# uC_power.net
KiCad netlist of a schematic drawn in EAGLE
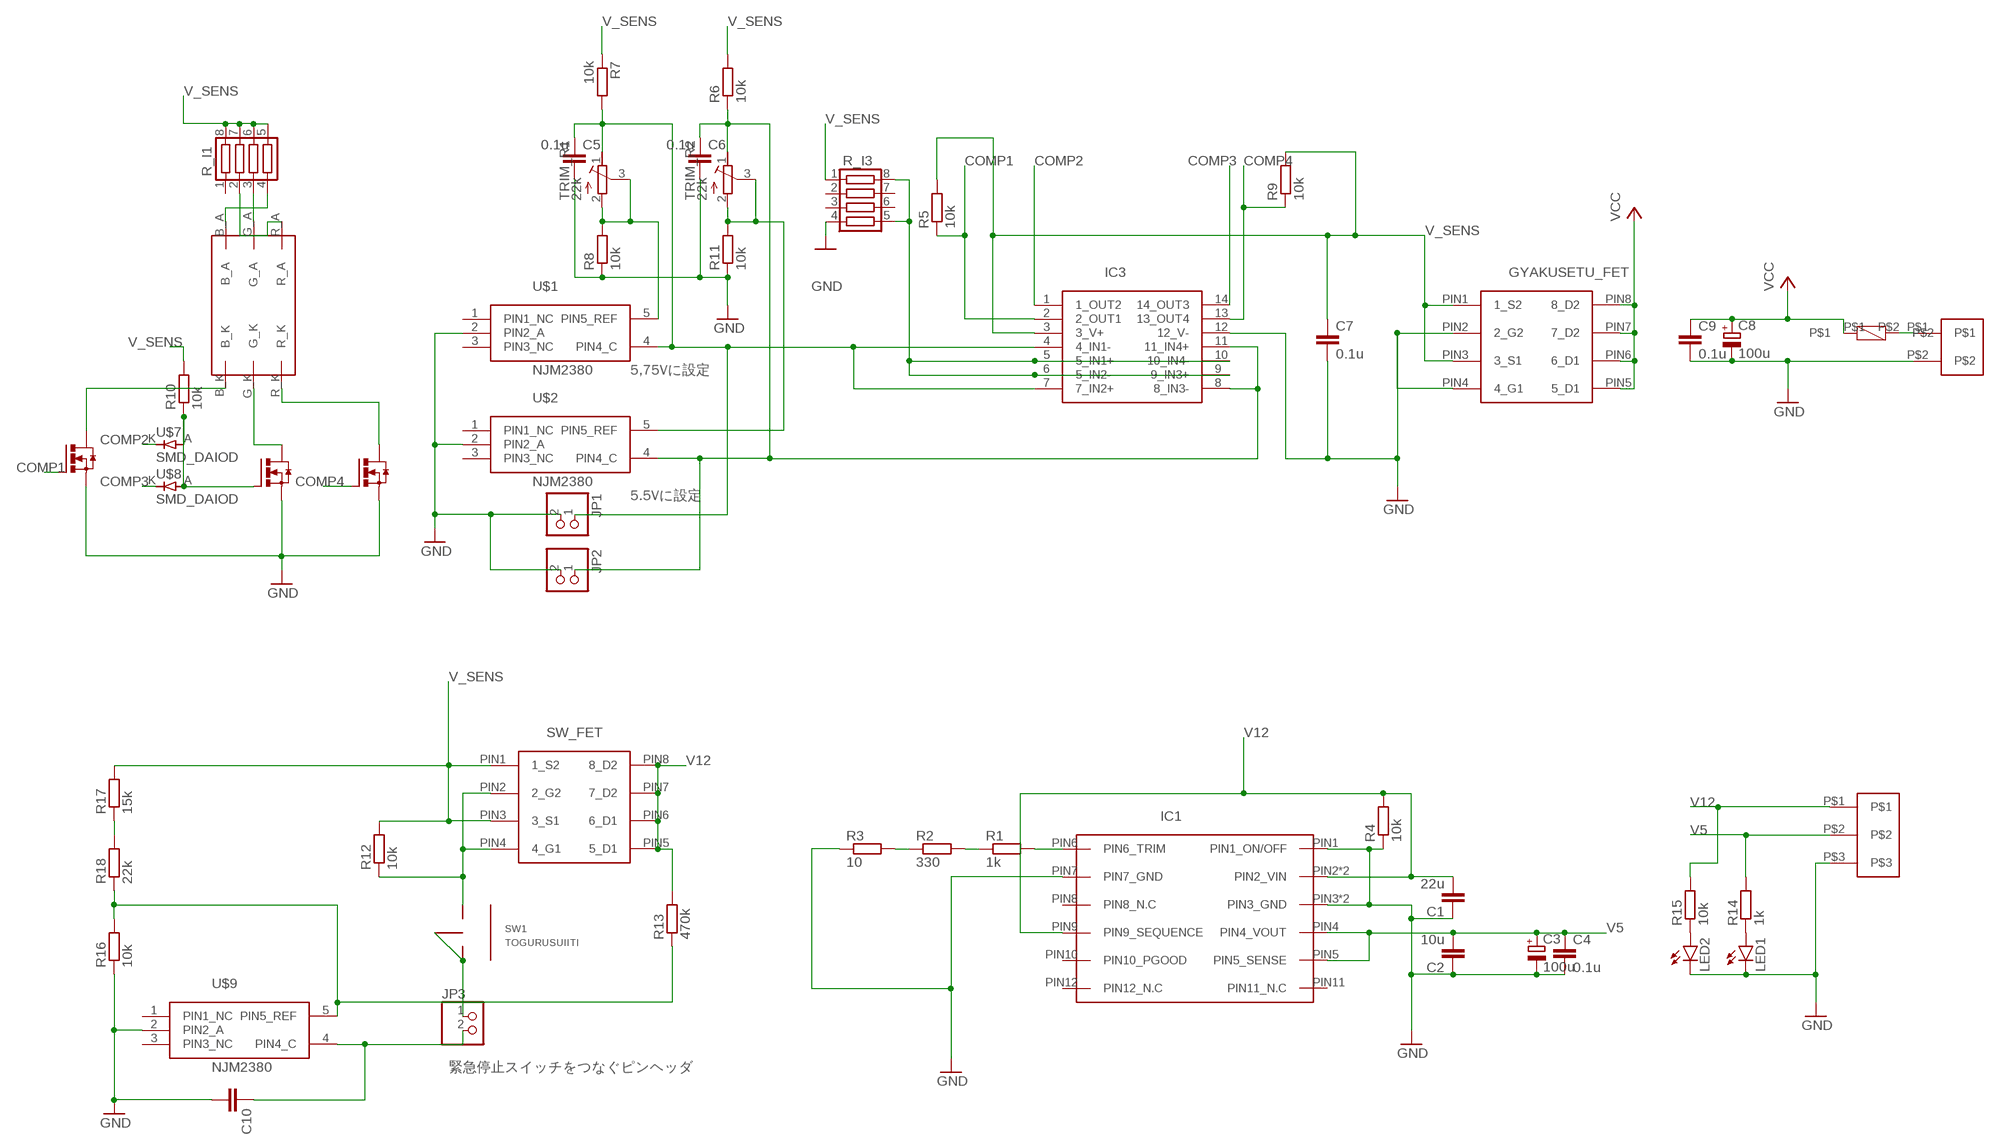
[diagram p0: schematic, sheet 1]

(export (version "E")
  (design (tool "Eeschema 10.0.6"))
  (components
    (comp (ref "C1")
      (value "22u")
      (footprint "eagle-import:C1608")
      (libsource (lib "eagle-import") (part "C-EUC1608"))
    )
    (comp (ref "C2")
      (value "10u")
      (footprint "eagle-import:C1608")
      (libsource (lib "eagle-import") (part "C-EUC1608"))
    )
    (comp (ref "C3")
      (value "100u")
      (footprint "eagle-import:153CLV-0605")
      (libsource (lib "eagle-import") (part "CPOL-EU153CLV-0605"))
    )
    (comp (ref "C4")
      (value "0.1u")
      (footprint "eagle-import:C1608")
      (libsource (lib "eagle-import") (part "C-EUC1608"))
    )
    (comp (ref "C5")
      (value "0.1u")
      (footprint "eagle-import:C1608")
      (libsource (lib "eagle-import") (part "C-EUC1608"))
    )
    (comp (ref "C6")
      (value "0.1u")
      (footprint "eagle-import:C1608")
      (libsource (lib "eagle-import") (part "C-EUC1608"))
    )
    (comp (ref "C7")
      (value "0.1u")
      (footprint "eagle-import:C1608")
      (libsource (lib "eagle-import") (part "C-EUC1608"))
    )
    (comp (ref "C8")
      (value "100u")
      (footprint "eagle-import:153CLV-0605")
      (libsource (lib "eagle-import") (part "CPOL-EU153CLV-0605"))
    )
    (comp (ref "C9")
      (value "0.1u")
      (footprint "eagle-import:C1608")
      (libsource (lib "eagle-import") (part "C-EUC1608"))
    )
    (comp (ref "C10")
      (value "C-EUC1608")
      (footprint "eagle-import:C1608")
      (libsource (lib "eagle-import") (part "C-EUC1608"))
    )
    (comp (ref "F1")
      (value "RGEF300")
      (footprint "eagle-import:RGEF300")
      (libsource (lib "eagle-import") (part "RGEF300"))
    )
    (comp (ref "GYAKUSETU_FET")
      (value "FDS4935A")
      (footprint "eagle-import:SOP8")
      (libsource (lib "eagle-import") (part "FDS4935A"))
    )
    (comp (ref "IC1")
      (value "MURATA_OKL-T/6-W12N-C")
      (footprint "eagle-import:OKL-T_6-W12N-C")
      (libsource (lib "eagle-import") (part "MURATA_OKL-T/6-W12N-C"))
    )
    (comp (ref "IC3")
      (value "UPC339GR")
      (footprint "eagle-import:TSSOP14")
      (libsource (lib "eagle-import") (part "UPC339GR"))
    )
    (comp (ref "JP1")
      (value "PINHD-1X2")
      (footprint "eagle-import:1X02")
      (libsource (lib "eagle-import") (part "PINHD-1X2"))
    )
    (comp (ref "JP2")
      (value "PINHD-1X2")
      (footprint "eagle-import:1X02")
      (libsource (lib "eagle-import") (part "PINHD-1X2"))
    )
    (comp (ref "JP3")
      (value "PINHD-1X2")
      (footprint "eagle-import:1X02")
      (libsource (lib "eagle-import") (part "PINHD-1X2"))
    )
    (comp (ref "LED1")
      (value "1608LED")
      (footprint "eagle-import:1608")
      (libsource (lib "eagle-import") (part "1608LED"))
    )
    (comp (ref "LED2")
      (value "1608LED")
      (footprint "eagle-import:1608")
      (libsource (lib "eagle-import") (part "1608LED"))
    )
    (comp (ref "R1")
      (value "1k")
      (footprint "eagle-import:1608")
      (libsource (lib "eagle-import") (part "R_REG"))
    )
    (comp (ref "R2")
      (value "330")
      (footprint "eagle-import:1608")
      (libsource (lib "eagle-import") (part "R_REG"))
    )
    (comp (ref "R3")
      (value "10")
      (footprint "eagle-import:1608")
      (libsource (lib "eagle-import") (part "R_REG"))
    )
    (comp (ref "R4")
      (value "10k")
      (footprint "eagle-import:1608")
      (libsource (lib "eagle-import") (part "R_REG"))
    )
    (comp (ref "R5")
      (value "10k")
      (footprint "eagle-import:1608")
      (libsource (lib "eagle-import") (part "R_REG"))
    )
    (comp (ref "R6")
      (value "10k")
      (footprint "eagle-import:1608")
      (libsource (lib "eagle-import") (part "R_REG"))
    )
    (comp (ref "R7")
      (value "10k")
      (footprint "eagle-import:1608")
      (libsource (lib "eagle-import") (part "R_REG"))
    )
    (comp (ref "R8")
      (value "10k")
      (footprint "eagle-import:1608")
      (libsource (lib "eagle-import") (part "R_REG"))
    )
    (comp (ref "R9")
      (value "10k")
      (footprint "eagle-import:1608")
      (libsource (lib "eagle-import") (part "R_REG"))
    )
    (comp (ref "R10")
      (value "10k")
      (footprint "eagle-import:1608")
      (libsource (lib "eagle-import") (part "R_REG"))
    )
    (comp (ref "R11")
      (value "10k")
      (footprint "eagle-import:1608")
      (libsource (lib "eagle-import") (part "R_REG"))
    )
    (comp (ref "R12")
      (value "10k")
      (footprint "eagle-import:1608")
      (libsource (lib "eagle-import") (part "R_REG"))
    )
    (comp (ref "R13")
      (value "470k")
      (footprint "eagle-import:1608")
      (libsource (lib "eagle-import") (part "R_REG"))
    )
    (comp (ref "R14")
      (value "1k")
      (footprint "eagle-import:1608")
      (libsource (lib "eagle-import") (part "R_REG"))
    )
    (comp (ref "R15")
      (value "10k")
      (footprint "eagle-import:1608")
      (libsource (lib "eagle-import") (part "R_REG"))
    )
    (comp (ref "R16")
      (value "10k")
      (footprint "eagle-import:1608")
      (libsource (lib "eagle-import") (part "R_REG"))
    )
    (comp (ref "R17")
      (value "15k")
      (footprint "eagle-import:1608")
      (libsource (lib "eagle-import") (part "R_REG"))
    )
    (comp (ref "R18")
      (value "22k")
      (footprint "eagle-import:1608")
      (libsource (lib "eagle-import") (part "R_REG"))
    )
    (comp (ref "R_I1")
      (value "R_SHUGOU2")
      (footprint "eagle-import:1005X4RESISTOR")
      (libsource (lib "eagle-import") (part "R_SHUGOU2"))
    )
    (comp (ref "R_I3")
      (value "R_SHUGOU2")
      (footprint "eagle-import:1005X4RESISTOR")
      (libsource (lib "eagle-import") (part "R_SHUGOU2"))
    )
    (comp (ref "SW1")
      (value "TOGURUSUIITI")
      (footprint "eagle-import:TOGURUSUIITI")
      (libsource (lib "eagle-import") (part "TOGURUSUIITI"))
    )
    (comp (ref "SW_FET")
      (value "FDS4935A")
      (footprint "eagle-import:SOP8")
      (libsource (lib "eagle-import") (part "FDS4935A"))
    )
    (comp (ref "TRIM_R1")
      (value "22k")
      (footprint "eagle-import:PV23A")
      (libsource (lib "eagle-import") (part "R_TRIM2"))
    )
    (comp (ref "TRIM_R2")
      (value "22k")
      (footprint "eagle-import:PV23A")
      (libsource (lib "eagle-import") (part "R_TRIM2"))
    )
    (comp (ref "U$1")
      (value "NJM2380")
      (footprint "eagle-import:SOT23-5")
      (libsource (lib "eagle-import") (part "NJM2380"))
    )
    (comp (ref "U$2")
      (value "NJM2380")
      (footprint "eagle-import:SOT23-5")
      (libsource (lib "eagle-import") (part "NJM2380"))
    )
    (comp (ref "U$3")
      (value "SOT23_NFET")
      (footprint "eagle-import:SOT23")
      (libsource (lib "eagle-import") (part "SOT23_NFET"))
    )
    (comp (ref "U$4")
      (value "SOT23_NFET")
      (footprint "eagle-import:SOT23")
      (libsource (lib "eagle-import") (part "SOT23_NFET"))
    )
    (comp (ref "U$5")
      (value "SOT23_NFET")
      (footprint "eagle-import:SOT23")
      (libsource (lib "eagle-import") (part "SOT23_NFET"))
    )
    (comp (ref "U$6")
      (value "RGB_LED")
      (footprint "eagle-import:RGB_LED")
      (libsource (lib "eagle-import") (part "RGB_LED"))
    )
    (comp (ref "U$7")
      (value "SMD_DAIOD")
      (footprint "eagle-import:SOD_123")
      (libsource (lib "eagle-import") (part "SMD_DAIOD"))
    )
    (comp (ref "U$8")
      (value "SMD_DAIOD")
      (footprint "eagle-import:SOD_123")
      (libsource (lib "eagle-import") (part "SMD_DAIOD"))
    )
    (comp (ref "U$9")
      (value "NJM2380")
      (footprint "eagle-import:SOT23-5")
      (libsource (lib "eagle-import") (part "NJM2380"))
    )
    (comp (ref "U$10")
      (value "YUROBLOCK3")
      (footprint "eagle-import:YUROBLOCK3")
      (libsource (lib "eagle-import") (part "YUROBLOCK3"))
    )
    (comp (ref "U$11")
      (value "YUROBLOCK2")
      (footprint "eagle-import:YUROBLOCK2")
      (libsource (lib "eagle-import") (part "YUROBLOCK2"))
    )
  )
  (nets
    (net (code "1") (name "/COMP1") (class "Default")
      (node (ref "IC3") (pin "2") (pinfunction "2_OUT1_2") (pintype "bidirectional"))
      (node (ref "R5") (pin "1") (pinfunction "1_1") (pintype "passive"))
      (node (ref "U$5") (pin "PIN1") (pinfunction "PIN1_G_PIN1") (pintype "passive"))
    )
    (net (code "2") (name "/COMP2") (class "Default")
      (node (ref "IC3") (pin "1") (pinfunction "1_OUT2_1") (pintype "bidirectional"))
      (node (ref "U$7") (pin "K") (pinfunction "C_K") (pintype "passive"))
    )
    (net (code "3") (name "/COMP3") (class "Default")
      (node (ref "IC3") (pin "14") (pinfunction "14_OUT3_14") (pintype "bidirectional"))
      (node (ref "U$8") (pin "K") (pinfunction "C_K") (pintype "passive"))
    )
    (net (code "4") (name "/COMP4") (class "Default")
      (node (ref "IC3") (pin "13") (pinfunction "13_OUT4_13") (pintype "bidirectional"))
      (node (ref "R9") (pin "1") (pinfunction "1_1") (pintype "passive"))
      (node (ref "U$3") (pin "PIN1") (pinfunction "PIN1_G_PIN1") (pintype "passive"))
    )
    (net (code "5") (name "/V5") (class "Default")
      (node (ref "C2") (pin "2") (pinfunction "2_2") (pintype "passive"))
      (node (ref "C3") (pin "+") (pinfunction "+_+") (pintype "passive"))
      (node (ref "C4") (pin "1") (pinfunction "1_1") (pintype "passive"))
      (node (ref "IC1") (pin "PIN4") (pinfunction "PIN4_VOUT_PIN4") (pintype "bidirectional"))
      (node (ref "IC1") (pin "PIN5") (pinfunction "PIN5_SENSE_PIN5") (pintype "bidirectional"))
      (node (ref "R14") (pin "2") (pinfunction "2_2") (pintype "passive"))
      (node (ref "U$10") (pin "P$2") (pinfunction "P$2_P$2") (pintype "bidirectional"))
    )
    (net (code "6") (name "/V12") (class "Default")
      (node (ref "C1") (pin "2") (pinfunction "2_2") (pintype "passive"))
      (node (ref "IC1") (pin "PIN2") (pinfunction "PIN2_VIN_PIN2") (pintype "bidirectional"))
      (node (ref "IC1") (pin "PIN2@2") (pinfunction "PIN2_VIN_PIN2@2") (pintype "bidirectional"))
      (node (ref "IC1") (pin "PIN9") (pinfunction "PIN9_SEQUENCE_PIN9") (pintype "bidirectional"))
      (node (ref "R13") (pin "2") (pinfunction "2_2") (pintype "passive"))
      (node (ref "R15") (pin "2") (pinfunction "2_2") (pintype "passive"))
      (node (ref "R4") (pin "2") (pinfunction "2_2") (pintype "passive"))
      (node (ref "SW_FET") (pin "PIN5") (pinfunction "5_D1_PIN5") (pintype "bidirectional"))
      (node (ref "SW_FET") (pin "PIN6") (pinfunction "6_D1_PIN6") (pintype "bidirectional"))
      (node (ref "SW_FET") (pin "PIN7") (pinfunction "7_D2_PIN7") (pintype "bidirectional"))
      (node (ref "SW_FET") (pin "PIN8") (pinfunction "8_D2_PIN8") (pintype "bidirectional"))
      (node (ref "U$10") (pin "P$1") (pinfunction "P$1_P$1") (pintype "bidirectional"))
    )
    (net (code "7") (name "/V_SENS") (class "Default")
      (node (ref "C7") (pin "1") (pinfunction "1_1") (pintype "passive"))
      (node (ref "GYAKUSETU_FET") (pin "PIN1") (pinfunction "1_S2_PIN1") (pintype "bidirectional"))
      (node (ref "GYAKUSETU_FET") (pin "PIN3") (pinfunction "3_S1_PIN3") (pintype "bidirectional"))
      (node (ref "IC3") (pin "3") (pinfunction "3_V+_3") (pintype "bidirectional"))
      (node (ref "R10") (pin "2") (pinfunction "2_2") (pintype "passive"))
      (node (ref "R12") (pin "2") (pinfunction "2_2") (pintype "passive"))
      (node (ref "R17") (pin "2") (pinfunction "2_2") (pintype "passive"))
      (node (ref "R5") (pin "2") (pinfunction "2_2") (pintype "passive"))
      (node (ref "R6") (pin "2") (pinfunction "2_2") (pintype "passive"))
      (node (ref "R7") (pin "1") (pinfunction "1_1") (pintype "passive"))
      (node (ref "R9") (pin "2") (pinfunction "2_2") (pintype "passive"))
      (node (ref "R_I1") (pin "5") (pinfunction "5_5") (pintype "passive"))
      (node (ref "R_I1") (pin "6") (pinfunction "6_6") (pintype "passive"))
      (node (ref "R_I1") (pin "7") (pinfunction "7_7") (pintype "passive"))
      (node (ref "R_I1") (pin "8") (pinfunction "8_8") (pintype "passive"))
      (node (ref "R_I3") (pin "1") (pinfunction "1_1") (pintype "passive"))
      (node (ref "SW_FET") (pin "PIN1") (pinfunction "1_S2_PIN1") (pintype "bidirectional"))
      (node (ref "SW_FET") (pin "PIN3") (pinfunction "3_S1_PIN3") (pintype "bidirectional"))
    )
    (net (code "8") (name "GND") (class "Default")
      (node (ref "C1") (pin "1") (pinfunction "1_1") (pintype "passive"))
      (node (ref "C10") (pin "2") (pinfunction "2_2") (pintype "passive"))
      (node (ref "C2") (pin "1") (pinfunction "1_1") (pintype "passive"))
      (node (ref "C3") (pin "-") (pinfunction "-_-") (pintype "passive"))
      (node (ref "C4") (pin "2") (pinfunction "2_2") (pintype "passive"))
      (node (ref "C5") (pin "2") (pinfunction "2_2") (pintype "passive"))
      (node (ref "C6") (pin "2") (pinfunction "2_2") (pintype "passive"))
      (node (ref "C7") (pin "2") (pinfunction "2_2") (pintype "passive"))
      (node (ref "C8") (pin "-") (pinfunction "-_-") (pintype "passive"))
      (node (ref "C9") (pin "2") (pinfunction "2_2") (pintype "passive"))
      (node (ref "GYAKUSETU_FET") (pin "PIN2") (pinfunction "2_G2_PIN2") (pintype "bidirectional"))
      (node (ref "GYAKUSETU_FET") (pin "PIN4") (pinfunction "4_G1_PIN4") (pintype "bidirectional"))
      (node (ref "IC1") (pin "PIN1") (pinfunction "PIN1_ON/OFF_PIN1") (pintype "bidirectional"))
      (node (ref "IC1") (pin "PIN3") (pinfunction "PIN3_GND_PIN3") (pintype "bidirectional"))
      (node (ref "IC1") (pin "PIN3@2") (pinfunction "PIN3_GND_PIN3@2") (pintype "bidirectional"))
      (node (ref "IC1") (pin "PIN7") (pinfunction "PIN7_GND_PIN7") (pintype "bidirectional"))
      (node (ref "IC3") (pin "12") (pinfunction "12_V-_12") (pintype "bidirectional"))
      (node (ref "JP1") (pin "2") (pinfunction "2_2") (pintype "passive"))
      (node (ref "JP2") (pin "2") (pinfunction "2_2") (pintype "passive"))
      (node (ref "LED1") (pin "K") (pinfunction "K_K") (pintype "passive"))
      (node (ref "LED2") (pin "K") (pinfunction "K_K") (pintype "passive"))
      (node (ref "R11") (pin "1") (pinfunction "1_1") (pintype "passive"))
      (node (ref "R16") (pin "1") (pinfunction "1_1") (pintype "passive"))
      (node (ref "R3") (pin "1") (pinfunction "1_1") (pintype "passive"))
      (node (ref "R4") (pin "1") (pinfunction "1_1") (pintype "passive"))
      (node (ref "R8") (pin "1") (pinfunction "1_1") (pintype "passive"))
      (node (ref "R_I3") (pin "4") (pinfunction "4_4") (pintype "passive"))
      (node (ref "U$1") (pin "2") (pinfunction "PIN2_A_2") (pintype "bidirectional"))
      (node (ref "U$10") (pin "P$3") (pinfunction "P$3_P$3") (pintype "bidirectional"))
      (node (ref "U$11") (pin "P$2") (pinfunction "P$2_P$2") (pintype "bidirectional"))
      (node (ref "U$2") (pin "2") (pinfunction "PIN2_A_2") (pintype "bidirectional"))
      (node (ref "U$3") (pin "PIN2") (pinfunction "PIN3_S_PIN2") (pintype "passive"))
      (node (ref "U$4") (pin "PIN2") (pinfunction "PIN3_S_PIN2") (pintype "passive"))
      (node (ref "U$5") (pin "PIN2") (pinfunction "PIN3_S_PIN2") (pintype "passive"))
      (node (ref "U$9") (pin "2") (pinfunction "PIN2_A_2") (pintype "bidirectional"))
    )
    (net (code "9") (name "Net-(F1-PadP$2)") (class "Default")
      (node (ref "F1") (pin "P$2") (pinfunction "P$2_P$2") (pintype "bidirectional"))
      (node (ref "U$11") (pin "P$1") (pinfunction "P$1_P$1") (pintype "bidirectional"))
    )
    (net (code "10") (name "Net-(IC1-PIN6_TRIM)") (class "Default")
      (node (ref "IC1") (pin "PIN6") (pinfunction "PIN6_TRIM_PIN6") (pintype "bidirectional"))
      (node (ref "R1") (pin "2") (pinfunction "2_2") (pintype "passive"))
    )
    (net (code "11") (name "Net-(IC3-4_IN1-)") (class "Default")
      (node (ref "C5") (pin "1") (pinfunction "1_1") (pintype "passive"))
      (node (ref "IC3") (pin "4") (pinfunction "4_IN1-_4") (pintype "bidirectional"))
      (node (ref "IC3") (pin "7") (pinfunction "7_IN2+_7") (pintype "bidirectional"))
      (node (ref "JP1") (pin "1") (pinfunction "1_1") (pintype "passive"))
      (node (ref "R7") (pin "2") (pinfunction "2_2") (pintype "passive"))
      (node (ref "TRIM_R1") (pin "1") (pinfunction "E_1") (pintype "passive"))
      (node (ref "U$1") (pin "4") (pinfunction "PIN4_C_4") (pintype "bidirectional"))
    )
    (net (code "12") (name "Net-(IC3-10_IN4-)") (class "Default")
      (node (ref "IC3") (pin "10") (pinfunction "10_IN4-_10") (pintype "bidirectional"))
      (node (ref "IC3") (pin "5") (pinfunction "5_IN1+_5") (pintype "bidirectional"))
      (node (ref "IC3") (pin "6") (pinfunction "5_IN2-_6") (pintype "bidirectional"))
      (node (ref "IC3") (pin "9") (pinfunction "9_IN3+_9") (pintype "bidirectional"))
      (node (ref "R_I3") (pin "5") (pinfunction "5_5") (pintype "passive"))
      (node (ref "R_I3") (pin "8") (pinfunction "8_8") (pintype "passive"))
    )
    (net (code "13") (name "Net-(IC3-11_IN4+)") (class "Default")
      (node (ref "C6") (pin "1") (pinfunction "1_1") (pintype "passive"))
      (node (ref "IC3") (pin "11") (pinfunction "11_IN4+_11") (pintype "bidirectional"))
      (node (ref "IC3") (pin "8") (pinfunction "8_IN3-_8") (pintype "bidirectional"))
      (node (ref "JP2") (pin "1") (pinfunction "1_1") (pintype "passive"))
      (node (ref "R6") (pin "1") (pinfunction "1_1") (pintype "passive"))
      (node (ref "TRIM_R2") (pin "1") (pinfunction "E_1") (pintype "passive"))
      (node (ref "U$2") (pin "4") (pinfunction "PIN4_C_4") (pintype "bidirectional"))
    )
    (net (code "14") (name "Net-(JP3-Pad1)") (class "Default")
      (node (ref "JP3") (pin "1") (pinfunction "1_1") (pintype "passive"))
      (node (ref "SW1") (pin "2") (pinfunction "2_2") (pintype "bidirectional"))
      (node (ref "SW1") (pin "C") (pinfunction "C_C") (pintype "bidirectional"))
    )
    (net (code "15") (name "Net-(LED1-PadA)") (class "Default")
      (node (ref "LED1") (pin "A") (pinfunction "A_A") (pintype "passive"))
      (node (ref "R14") (pin "1") (pinfunction "1_1") (pintype "passive"))
    )
    (net (code "16") (name "Net-(LED2-PadA)") (class "Default")
      (node (ref "LED2") (pin "A") (pinfunction "A_A") (pintype "passive"))
      (node (ref "R15") (pin "1") (pinfunction "1_1") (pintype "passive"))
    )
    (net (code "17") (name "Net-(R1-Pad1)") (class "Default")
      (node (ref "R1") (pin "1") (pinfunction "1_1") (pintype "passive"))
      (node (ref "R2") (pin "2") (pinfunction "2_2") (pintype "passive"))
    )
    (net (code "18") (name "Net-(R2-Pad1)") (class "Default")
      (node (ref "R2") (pin "1") (pinfunction "1_1") (pintype "passive"))
      (node (ref "R3") (pin "2") (pinfunction "2_2") (pintype "passive"))
    )
    (net (code "19") (name "Net-(R17-Pad1)") (class "Default")
      (node (ref "R17") (pin "1") (pinfunction "1_1") (pintype "passive"))
      (node (ref "R18") (pin "2") (pinfunction "2_2") (pintype "passive"))
    )
    (net (code "20") (name "Net-(R_I1-Pad2)") (class "Default")
      (node (ref "R_I1") (pin "2") (pinfunction "2_2") (pintype "passive"))
      (node (ref "U$6") (pin "R_A") (pinfunction "R_A_R_A") (pintype "bidirectional"))
    )
    (net (code "21") (name "Net-(R_I1-Pad3)") (class "Default")
      (node (ref "R_I1") (pin "3") (pinfunction "3_3") (pintype "passive"))
      (node (ref "U$6") (pin "G_A") (pinfunction "G_A_G_A") (pintype "bidirectional"))
    )
    (net (code "22") (name "Net-(R_I1-Pad4)") (class "Default")
      (node (ref "R_I1") (pin "4") (pinfunction "4_4") (pintype "passive"))
      (node (ref "U$6") (pin "B_A") (pinfunction "B_A_B_A") (pintype "bidirectional"))
    )
    (net (code "23") (name "Net-(SW_FET-2_G2)") (class "Default")
      (node (ref "R12") (pin "1") (pinfunction "1_1") (pintype "passive"))
      (node (ref "SW1") (pin "1") (pinfunction "1_1") (pintype "bidirectional"))
      (node (ref "SW_FET") (pin "PIN2") (pinfunction "2_G2_PIN2") (pintype "bidirectional"))
      (node (ref "SW_FET") (pin "PIN4") (pinfunction "4_G1_PIN4") (pintype "bidirectional"))
    )
    (net (code "24") (name "Net-(TRIM_R1-A)") (class "Default")
      (node (ref "R8") (pin "2") (pinfunction "2_2") (pintype "passive"))
      (node (ref "TRIM_R1") (pin "2") (pinfunction "A_2") (pintype "passive"))
      (node (ref "TRIM_R1") (pin "3") (pinfunction "S_3") (pintype "passive"))
      (node (ref "U$1") (pin "5") (pinfunction "PIN5_REF_5") (pintype "bidirectional"))
    )
    (net (code "25") (name "Net-(TRIM_R2-A)") (class "Default")
      (node (ref "R11") (pin "2") (pinfunction "2_2") (pintype "passive"))
      (node (ref "TRIM_R2") (pin "2") (pinfunction "A_2") (pintype "passive"))
      (node (ref "TRIM_R2") (pin "3") (pinfunction "S_3") (pintype "passive"))
      (node (ref "U$2") (pin "5") (pinfunction "PIN5_REF_5") (pintype "bidirectional"))
    )
    (net (code "26") (name "Net-(U$3-PIN2_D)") (class "Default")
      (node (ref "U$3") (pin "PIN3") (pinfunction "PIN2_D_PIN3") (pintype "passive"))
      (node (ref "U$6") (pin "R_K") (pinfunction "R_K_R_K") (pintype "bidirectional"))
    )
    (net (code "27") (name "Net-(U$4-PIN1_G)") (class "Default")
      (node (ref "R10") (pin "1") (pinfunction "1_1") (pintype "passive"))
      (node (ref "U$4") (pin "PIN1") (pinfunction "PIN1_G_PIN1") (pintype "passive"))
      (node (ref "U$7") (pin "A") (pinfunction "A_A") (pintype "passive"))
      (node (ref "U$8") (pin "A") (pinfunction "A_A") (pintype "passive"))
    )
    (net (code "28") (name "Net-(U$4-PIN2_D)") (class "Default")
      (node (ref "U$4") (pin "PIN3") (pinfunction "PIN2_D_PIN3") (pintype "passive"))
      (node (ref "U$6") (pin "G_K") (pinfunction "G_K_G_K") (pintype "bidirectional"))
    )
    (net (code "29") (name "Net-(U$5-PIN2_D)") (class "Default")
      (node (ref "U$5") (pin "PIN3") (pinfunction "PIN2_D_PIN3") (pintype "passive"))
      (node (ref "U$6") (pin "B_K") (pinfunction "B_K_B_K") (pintype "bidirectional"))
    )
    (net (code "30") (name "Net-(U$9-PIN4_C)") (class "Default")
      (node (ref "C10") (pin "1") (pinfunction "1_1") (pintype "passive"))
      (node (ref "JP3") (pin "2") (pinfunction "2_2") (pintype "passive"))
      (node (ref "U$9") (pin "4") (pinfunction "PIN4_C_4") (pintype "bidirectional"))
    )
    (net (code "31") (name "Net-(U$9-PIN5_REF)") (class "Default")
      (node (ref "R13") (pin "1") (pinfunction "1_1") (pintype "passive"))
      (node (ref "R16") (pin "2") (pinfunction "2_2") (pintype "passive"))
      (node (ref "R18") (pin "1") (pinfunction "1_1") (pintype "passive"))
      (node (ref "U$9") (pin "5") (pinfunction "PIN5_REF_5") (pintype "bidirectional"))
    )
    (net (code "32") (name "VCC") (class "Default")
      (node (ref "C8") (pin "+") (pinfunction "+_+") (pintype "passive"))
      (node (ref "C9") (pin "1") (pinfunction "1_1") (pintype "passive"))
      (node (ref "F1") (pin "P$1") (pinfunction "P$1_P$1") (pintype "bidirectional"))
      (node (ref "GYAKUSETU_FET") (pin "PIN5") (pinfunction "5_D1_PIN5") (pintype "bidirectional"))
      (node (ref "GYAKUSETU_FET") (pin "PIN6") (pinfunction "6_D1_PIN6") (pintype "bidirectional"))
      (node (ref "GYAKUSETU_FET") (pin "PIN7") (pinfunction "7_D2_PIN7") (pintype "bidirectional"))
      (node (ref "GYAKUSETU_FET") (pin "PIN8") (pinfunction "8_D2_PIN8") (pintype "bidirectional"))
    )
    (net (code "33") (name "unconnected-(IC1-PIN8_N.C-PadPIN8)") (class "Default")
      (node (ref "IC1") (pin "PIN8") (pinfunction "PIN8_N.C_PIN8") (pintype "bidirectional"))
    )
    (net (code "34") (name "unconnected-(IC1-PIN10_PGOOD-PadPIN10)") (class "Default")
      (node (ref "IC1") (pin "PIN10") (pinfunction "PIN10_PGOOD_PIN10") (pintype "bidirectional"))
    )
    (net (code "35") (name "unconnected-(IC1-PIN11_N.C-PadPIN11)") (class "Default")
      (node (ref "IC1") (pin "PIN11") (pinfunction "PIN11_N.C_PIN11") (pintype "bidirectional"))
    )
    (net (code "36") (name "unconnected-(IC1-PIN12_N.C-PadPIN12)") (class "Default")
      (node (ref "IC1") (pin "PIN12") (pinfunction "PIN12_N.C_PIN12") (pintype "bidirectional"))
    )
    (net (code "37") (name "unconnected-(R_I1-Pad1)") (class "Default")
      (node (ref "R_I1") (pin "1") (pinfunction "1_1") (pintype "passive"))
    )
    (net (code "38") (name "unconnected-(R_I3-Pad2)") (class "Default")
      (node (ref "R_I3") (pin "2") (pinfunction "2_2") (pintype "passive"))
    )
    (net (code "39") (name "unconnected-(R_I3-Pad3)") (class "Default")
      (node (ref "R_I3") (pin "3") (pinfunction "3_3") (pintype "passive"))
    )
    (net (code "40") (name "unconnected-(R_I3-Pad6)") (class "Default")
      (node (ref "R_I3") (pin "6") (pinfunction "6_6") (pintype "passive"))
    )
    (net (code "41") (name "unconnected-(R_I3-Pad7)") (class "Default")
      (node (ref "R_I3") (pin "7") (pinfunction "7_7") (pintype "passive"))
    )
    (net (code "42") (name "unconnected-(SW1-NC-PadNC@2)") (class "Default")
      (node (ref "SW1") (pin "NC@2") (pinfunction "NC_NC@2") (pintype "bidirectional"))
    )
    (net (code "43") (name "unconnected-(SW1-PadNC)") (class "Default")
      (node (ref "SW1") (pin "NC") (pinfunction "NC_NC") (pintype "bidirectional"))
    )
    (net (code "44") (name "unconnected-(U$1-PIN1_NC-Pad1)") (class "Default")
      (node (ref "U$1") (pin "1") (pinfunction "PIN1_NC_1") (pintype "bidirectional"))
    )
    (net (code "45") (name "unconnected-(U$1-PIN3_NC-Pad3)") (class "Default")
      (node (ref "U$1") (pin "3") (pinfunction "PIN3_NC_3") (pintype "bidirectional"))
    )
    (net (code "46") (name "unconnected-(U$2-PIN1_NC-Pad1)") (class "Default")
      (node (ref "U$2") (pin "1") (pinfunction "PIN1_NC_1") (pintype "bidirectional"))
    )
    (net (code "47") (name "unconnected-(U$2-PIN3_NC-Pad3)") (class "Default")
      (node (ref "U$2") (pin "3") (pinfunction "PIN3_NC_3") (pintype "bidirectional"))
    )
    (net (code "48") (name "unconnected-(U$9-PIN1_NC-Pad1)") (class "Default")
      (node (ref "U$9") (pin "1") (pinfunction "PIN1_NC_1") (pintype "bidirectional"))
    )
    (net (code "49") (name "unconnected-(U$9-PIN3_NC-Pad3)") (class "Default")
      (node (ref "U$9") (pin "3") (pinfunction "PIN3_NC_3") (pintype "bidirectional"))
    )
  )
)
